# VREG_AOZ1021AI_5V_3A.net
KiCad netlist of a schematic drawn in Altium Designer
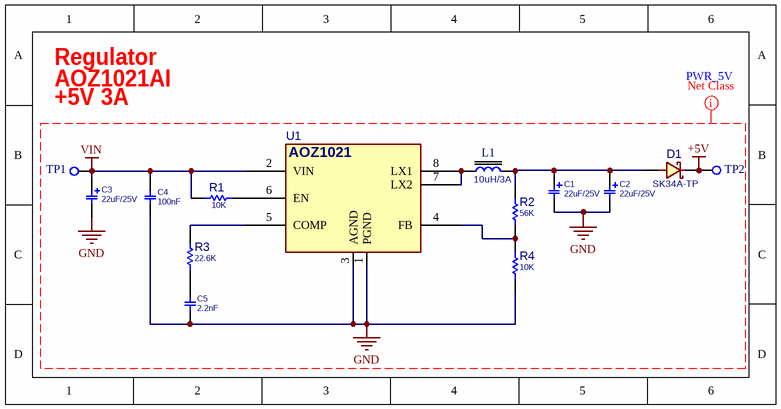
[diagram p0: VREG AOZ1021AI +5V 3A.SchDoc]

(export (version "E")
  (design (tool "Eeschema 10.0.6"))
  (components
    (comp (ref "C1")
      (value "22uF/25V")
      (footprint "C_TN_3216")
      (description "CAP, SMD, TAN")
      (libsource (lib "Passive") (part "CAP_SMD_TAN"))
    )
    (comp (ref "C2")
      (value "22uF/25V")
      (footprint "C_TN_3216")
      (description "CAP, SMD, TAN")
      (libsource (lib "Passive") (part "CAP_SMD_TAN"))
    )
    (comp (ref "C3")
      (value "22uF/25V")
      (footprint "C_TN_3216")
      (description "CAP, SMD, TAN")
      (libsource (lib "Passive") (part "CAP_SMD_TAN"))
    )
    (comp (ref "C4")
      (value "100nF")
      (footprint "C0603S")
      (description "CAP, SMD, MLCC")
      (fields (field (name "MANF_P#") "MANF_PART#") (field (name "MANF") "Murata"))
      (libsource (lib "Passive") (part "CAP_SMD_MLCC"))
    )
    (comp (ref "C5")
      (value "2.2nF")
      (footprint "C0603S")
      (description "CAP, SMD, MLCC")
      (fields (field (name "MANF_P#") "MANF_PART#") (field (name "MANF") "Murata"))
      (libsource (lib "Passive") (part "CAP_SMD_MLCC"))
    )
    (comp (ref "D1")
      (value "SK34A-TP")
      (footprint "D_SMA")
      (description "DIODE, SCHOTTKY, 40V, 3A")
      (fields (field (name "MANF") "Vishay") (field (name "MANF_P#") "SS14-E3"))
      (libsource (lib "PW Components") (part "DIODE_SMD_SCHOTTKY_SK34A-TP"))
    )
    (comp (ref "L1")
      (value "10uH/3A")
      (footprint "L_8")
      (description "IND, PWR, SMD")
      (libsource (lib "Passive") (part "INDPWR_SMD"))
    )
    (comp (ref "R1")
      (value "10K")
      (footprint "R0603S")
      (description "RES, SMD")
      (fields (field (name "MANF_P#") "RK73H1ETTP4701F") (field (name "MANF") "KOA SPEER"))
      (libsource (lib "Passive") (part "RES_SMD"))
    )
    (comp (ref "R2")
      (value "56K")
      (footprint "R0603S")
      (description "RES, SMD")
      (fields (field (name "MANF_P#") "RK73H1ETTP4701F") (field (name "MANF") "KOA SPEER"))
      (libsource (lib "Passive") (part "RES_SMD"))
    )
    (comp (ref "R3")
      (value "22.6K")
      (footprint "R0603S")
      (description "RES, SMD")
      (fields (field (name "MANF_P#") "RK73H1ETTP4701F") (field (name "MANF") "KOA SPEER"))
      (libsource (lib "Passive") (part "RES_SMD"))
    )
    (comp (ref "R4")
      (value "10K")
      (footprint "R0603S")
      (description "RES, SMD")
      (fields (field (name "MANF_P#") "RK73H1ETTP4701F") (field (name "MANF") "KOA SPEER"))
      (libsource (lib "Passive") (part "RES_SMD"))
    )
    (comp (ref "TP1")
      (value "Test Point")
      (footprint "TPSMD_C1")
      (libsource (lib "PW Components") (part "Test Point"))
    )
    (comp (ref "TP2")
      (value "Test Point")
      (footprint "TPSMD_C1")
      (libsource (lib "PW Components") (part "Test Point"))
    )
    (comp (ref "U1")
      (value "AOZ1021AI")
      (footprint "SO_8")
      (description "REG, Switching, Buck, 3A, ADJ, 500KHz, 4.5~16VIN, SO-8")
      (fields (field (name "MANF") "AOSMD"))
      (libsource (lib "PW Components") (part "VREG_AOZ1021AI_SO8"))
    )
  )
  (nets
    (net (code "1") (name "+5V") (class "Default")
      (node (ref "D1") (pin "2") (pinfunction "2_2") (pintype "passive"))
      (node (ref "TP2") (pin "1") (pinfunction "TP_1") (pintype "passive"))
    )
    (net (code "2") (name "GND") (class "Default")
      (node (ref "C1") (pin "2") (pinfunction "2_2") (pintype "passive"))
      (node (ref "C2") (pin "2") (pinfunction "2_2") (pintype "passive"))
      (node (ref "C3") (pin "2") (pinfunction "2_2") (pintype "passive"))
      (node (ref "C4") (pin "1") (pinfunction "1_1") (pintype "passive"))
      (node (ref "C5") (pin "1") (pinfunction "1_1") (pintype "passive"))
      (node (ref "R4") (pin "2") (pinfunction "2_2") (pintype "passive"))
      (node (ref "U1") (pin "1") (pinfunction "PGND_1") (pintype "power_in"))
      (node (ref "U1") (pin "3") (pinfunction "AGND_3") (pintype "power_in"))
    )
    (net (code "3") (name "Net-(C1-Pad1)") (class "Default")
      (node (ref "C1") (pin "1") (pinfunction "1_1") (pintype "passive"))
      (node (ref "C2") (pin "1") (pinfunction "1_1") (pintype "passive"))
      (node (ref "D1") (pin "1") (pinfunction "1_1") (pintype "passive"))
      (node (ref "L1") (pin "2") (pinfunction "2_2") (pintype "passive"))
      (node (ref "R2") (pin "1") (pinfunction "1_1") (pintype "passive"))
    )
    (net (code "4") (name "Net-(C5-Pad2)") (class "Default")
      (node (ref "C5") (pin "2") (pinfunction "2_2") (pintype "passive"))
      (node (ref "R3") (pin "2") (pinfunction "2_2") (pintype "passive"))
    )
    (net (code "5") (name "Net-(U1-COMP)") (class "Default")
      (node (ref "R3") (pin "1") (pinfunction "1_1") (pintype "passive"))
      (node (ref "U1") (pin "5") (pinfunction "COMP_5") (pintype "passive"))
    )
    (net (code "6") (name "Net-(U1-EN)") (class "Default")
      (node (ref "R1") (pin "1") (pinfunction "1_1") (pintype "passive"))
      (node (ref "U1") (pin "6") (pinfunction "EN_6") (pintype "passive"))
    )
    (net (code "7") (name "Net-(U1-FB)") (class "Default")
      (node (ref "R2") (pin "2") (pinfunction "2_2") (pintype "passive"))
      (node (ref "R4") (pin "1") (pinfunction "1_1") (pintype "passive"))
      (node (ref "U1") (pin "4") (pinfunction "FB_4") (pintype "passive"))
    )
    (net (code "8") (name "Net-(U1-LX1)") (class "Default")
      (node (ref "L1") (pin "1") (pinfunction "1_1") (pintype "passive"))
      (node (ref "U1") (pin "7") (pinfunction "LX2_7") (pintype "passive"))
      (node (ref "U1") (pin "8") (pinfunction "LX1_8") (pintype "passive"))
    )
    (net (code "9") (name "VIN") (class "Default")
      (node (ref "C3") (pin "1") (pinfunction "1_1") (pintype "passive"))
      (node (ref "C4") (pin "2") (pinfunction "2_2") (pintype "passive"))
      (node (ref "R1") (pin "2") (pinfunction "2_2") (pintype "passive"))
      (node (ref "TP1") (pin "1") (pinfunction "TP_1") (pintype "passive"))
      (node (ref "U1") (pin "2") (pinfunction "VIN_2") (pintype "power_in"))
    )
  )
)
